# Sensor-PCB.net
KiCad netlist of a schematic drawn in Altium Designer
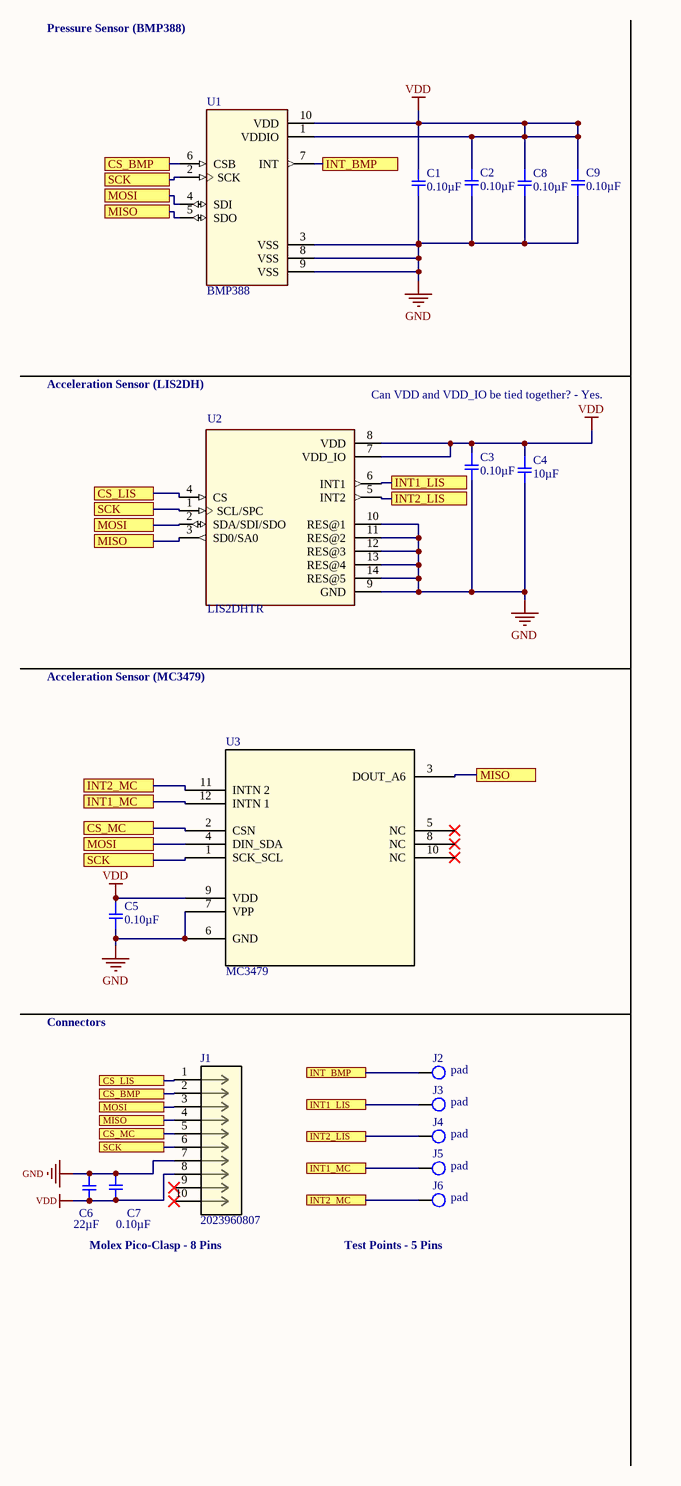
[diagram p0: Sensor-PCB.SchDoc]

(export (version "E")
  (design (tool "Eeschema 10.0.6"))
  (components
    (comp (ref "C1")
      (value "0.10µF")
      (footprint "SMD-0603C")
      (description "CAP CER 0.1UF 16V X7R 0603")
      (fields
        (field (name "DIGI-KEY PART NUMBER") "490-5796-1-ND")
        (field (name "PART NUMBER") "GCJ188R71C104KA01D")
      )
      (libsource (lib "capacitor_murata_0603") (part "GCJ188R71C104KA01D"))
    )
    (comp (ref "C2")
      (value "0.10µF")
      (footprint "SMD-0603C")
      (description "CAP CER 0.1UF 16V X7R 0603")
      (fields
        (field (name "DIGI-KEY PART NUMBER") "490-5796-1-ND")
        (field (name "PART NUMBER") "GCJ188R71C104KA01D")
      )
      (libsource (lib "capacitor_murata_0603") (part "GCJ188R71C104KA01D"))
    )
    (comp (ref "C3")
      (value "0.10µF")
      (footprint "SMD-0603C")
      (description "CAP CER 0.1UF 16V X7R 0603")
      (fields
        (field (name "DIGI-KEY PART NUMBER") "490-5796-1-ND")
        (field (name "PART NUMBER") "GCJ188R71C104KA01D")
      )
      (libsource (lib "capacitor_murata_0603") (part "GCJ188R71C104KA01D"))
    )
    (comp (ref "C4")
      (value "10µF")
      (footprint "SMD-0603C")
      (description "CAP CER 10UF 10V X6S 0603")
      (fields
        (field (name "DIGI-KEY PART NUMBER") "490-7197-1-ND")
        (field (name "PART NUMBER") "GRM188C81A106MA73D")
      )
      (libsource (lib "capacitor_murata_0603") (part "GRM188C81A106MA73D"))
    )
    (comp (ref "C5")
      (value "0.10µF")
      (footprint "SMD-0603C")
      (description "CAP CER 0.1UF 16V X7R 0603")
      (fields
        (field (name "DIGI-KEY PART NUMBER") "490-5796-1-ND")
        (field (name "PART NUMBER") "GCJ188R71C104KA01D")
      )
      (libsource (lib "capacitor_murata_0603") (part "GCJ188R71C104KA01D"))
    )
    (comp (ref "C6")
      (value "22µF")
      (footprint "SMD-0603C")
      (description "CAP CER 22UF 10V X5R 0603")
      (fields
        (field (name "DIGI-KEY PART NUMBER") "490-10476-1-ND")
        (field (name "PART NUMBER") "GRM188R61A226ME15D")
      )
      (libsource (lib "capacitor_murata_0603") (part "GRM188R61A226ME15D"))
    )
    (comp (ref "C7")
      (value "0.10µF")
      (footprint "SMD-0603C")
      (description "CAP CER 0.1UF 16V X7R 0603")
      (fields
        (field (name "DIGI-KEY PART NUMBER") "490-5796-1-ND")
        (field (name "PART NUMBER") "GCJ188R71C104KA01D")
      )
      (libsource (lib "capacitor_murata_0603") (part "GCJ188R71C104KA01D"))
    )
    (comp (ref "C8")
      (value "0.10µF")
      (footprint "SMD-0603C")
      (description "CAP CER 0.1UF 16V X7R 0603")
      (fields
        (field (name "DIGI-KEY PART NUMBER") "490-5796-1-ND")
        (field (name "PART NUMBER") "GCJ188R71C104KA01D")
      )
      (libsource (lib "capacitor_murata_0603") (part "GCJ188R71C104KA01D"))
    )
    (comp (ref "C9")
      (value "0.10µF")
      (footprint "SMD-0603C")
      (description "CAP CER 0.1UF 16V X7R 0603")
      (fields
        (field (name "DIGI-KEY PART NUMBER") "490-5796-1-ND")
        (field (name "PART NUMBER") "GCJ188R71C104KA01D")
      )
      (libsource (lib "capacitor_murata_0603") (part "GCJ188R71C104KA01D"))
    )
    (comp (ref "J1")
      (value "2023960807")
      (footprint "siplab_custom_parts:CON_2023960807")
      (description "No Description Available")
      (fields (field (name "COPYRIGHT") "Copyright (C) 2021 Ultra Librarian. All rights reserved."))
      (libsource (lib "2023960807") (part "2023960807"))
    )
    (comp (ref "J2")
      (value "pad")
      (footprint "pad rect 1.5x3mm - duplicate")
      (libsource (lib "siplab_custom_parts") (part "pad"))
    )
    (comp (ref "J3")
      (value "pad")
      (footprint "pad rect 1.5x3mm - duplicate")
      (libsource (lib "siplab_custom_parts") (part "pad"))
    )
    (comp (ref "J4")
      (value "pad")
      (footprint "pad rect 1.5x3mm - duplicate")
      (libsource (lib "siplab_custom_parts") (part "pad"))
    )
    (comp (ref "J5")
      (value "pad")
      (footprint "pad rect 1.5x3mm - duplicate")
      (libsource (lib "siplab_custom_parts") (part "pad"))
    )
    (comp (ref "J6")
      (value "pad")
      (footprint "pad rect 1.5x3mm - duplicate")
      (libsource (lib "siplab_custom_parts") (part "pad"))
    )
    (comp (ref "U1")
      (value "BMP388")
      (footprint "*PQFN50P200X200X80-10N")
      (description "P-Sensor SPI I2C 1, 25 Bar SMD")
      (fields (field (name "MF") "Bosch Sensortec") (field (name "DIGI-KEY_PART_NUMBER") "828-1079-1-ND"))
      (libsource (lib "siplab_custom_parts") (part "BMP388"))
    )
    (comp (ref "U2")
      (value "LIS2DHTR")
      (footprint "*PQFN35P200X200X100-14N")
      (description "ACCEL 2-16G I2C/SPI 14LGA")
      (fields
        (field (name "DIGI-KEY PART NUMBER") "497-13795-1-ND")
        (field (name "MANUFACTURER") "STMicroelectronics")
      )
      (libsource (lib "siplab_custom_parts") (part "LIS2DHTR"))
    )
    (comp (ref "U3")
      (value "MC3479")
      (footprint "MC3479_MEM")
      (description "No Description Available")
      (fields (field (name "COPYRIGHT") "Copyright (C) 2021 Ultra Librarian. All rights reserved."))
      (libsource (lib "siplab_custom_parts") (part "MC3479"))
    )
  )
  (nets
    (net (code "1") (name "/CS_BMP") (class "Default")
      (node (ref "J1") (pin "2") (pinfunction "2_2") (pintype "passive"))
      (node (ref "U1") (pin "6") (pinfunction "CSB_6") (pintype "input"))
    )
    (net (code "2") (name "/CS_LIS") (class "Default")
      (node (ref "J1") (pin "1") (pinfunction "1_1") (pintype "passive"))
      (node (ref "U2") (pin "4") (pinfunction "CS_4") (pintype "input"))
    )
    (net (code "3") (name "/CS_MC") (class "Default")
      (node (ref "J1") (pin "5") (pinfunction "5_5") (pintype "passive"))
      (node (ref "U3") (pin "2") (pinfunction "CSN_2") (pintype "passive"))
    )
    (net (code "4") (name "/INT1_LIS") (class "Default")
      (node (ref "J3") (pin "1") (pinfunction "1_1") (pintype "passive"))
      (node (ref "U2") (pin "6") (pinfunction "INT1_6") (pintype "output"))
    )
    (net (code "5") (name "/INT1_MC") (class "Default")
      (node (ref "J5") (pin "1") (pinfunction "1_1") (pintype "passive"))
      (node (ref "U3") (pin "12") (pinfunction "INTN_1_12") (pintype "passive"))
    )
    (net (code "6") (name "/INT2_LIS") (class "Default")
      (node (ref "J4") (pin "1") (pinfunction "1_1") (pintype "passive"))
      (node (ref "U2") (pin "5") (pinfunction "INT2_5") (pintype "output"))
    )
    (net (code "7") (name "/INT2_MC") (class "Default")
      (node (ref "J6") (pin "1") (pinfunction "1_1") (pintype "passive"))
      (node (ref "U3") (pin "11") (pinfunction "INTN_2_11") (pintype "passive"))
    )
    (net (code "8") (name "/INT_BMP") (class "Default")
      (node (ref "J2") (pin "1") (pinfunction "1_1") (pintype "passive"))
      (node (ref "U1") (pin "7") (pinfunction "INT_7") (pintype "output"))
    )
    (net (code "9") (name "/MISO") (class "Default")
      (node (ref "J1") (pin "4") (pinfunction "4_4") (pintype "passive"))
      (node (ref "U1") (pin "5") (pinfunction "SDO_5") (pintype "bidirectional"))
      (node (ref "U2") (pin "3") (pinfunction "SD0/SA0_3") (pintype "output"))
      (node (ref "U3") (pin "3") (pinfunction "DOUT_A6_3") (pintype "passive"))
    )
    (net (code "10") (name "/MOSI") (class "Default")
      (node (ref "J1") (pin "3") (pinfunction "3_3") (pintype "passive"))
      (node (ref "U1") (pin "4") (pinfunction "SDI_4") (pintype "bidirectional"))
      (node (ref "U2") (pin "2") (pinfunction "SDA/SDI/SDO_2") (pintype "bidirectional"))
      (node (ref "U3") (pin "4") (pinfunction "DIN_SDA_4") (pintype "passive"))
    )
    (net (code "11") (name "/SCK") (class "Default")
      (node (ref "J1") (pin "6") (pinfunction "6_6") (pintype "passive"))
      (node (ref "U1") (pin "2") (pinfunction "SCK_2") (pintype "input"))
      (node (ref "U2") (pin "1") (pinfunction "SCL/SPC_1") (pintype "input"))
      (node (ref "U3") (pin "1") (pinfunction "SCK_SCL_1") (pintype "passive"))
    )
    (net (code "12") (name "GND") (class "Default")
      (node (ref "C1") (pin "2") (pinfunction "2_2") (pintype "passive"))
      (node (ref "C2") (pin "2") (pinfunction "2_2") (pintype "passive"))
      (node (ref "C3") (pin "2") (pinfunction "2_2") (pintype "passive"))
      (node (ref "C4") (pin "2") (pinfunction "2_2") (pintype "passive"))
      (node (ref "C5") (pin "2") (pinfunction "2_2") (pintype "passive"))
      (node (ref "C6") (pin "1") (pinfunction "1_1") (pintype "passive"))
      (node (ref "C7") (pin "1") (pinfunction "1_1") (pintype "passive"))
      (node (ref "C8") (pin "2") (pinfunction "2_2") (pintype "passive"))
      (node (ref "C9") (pin "2") (pinfunction "2_2") (pintype "passive"))
      (node (ref "J1") (pin "7") (pinfunction "7_7") (pintype "passive"))
      (node (ref "U1") (pin "3") (pinfunction "VSS_3") (pintype "power_in"))
      (node (ref "U1") (pin "8") (pinfunction "VSS_8") (pintype "power_in"))
      (node (ref "U1") (pin "9") (pinfunction "VSS_9") (pintype "power_in"))
      (node (ref "U2") (pin "10") (pinfunction "RES@1_10") (pintype "power_in"))
      (node (ref "U2") (pin "11") (pinfunction "RES@2_11") (pintype "power_in"))
      (node (ref "U2") (pin "12") (pinfunction "RES@3_12") (pintype "power_in"))
      (node (ref "U2") (pin "13") (pinfunction "RES@4_13") (pintype "power_in"))
      (node (ref "U2") (pin "14") (pinfunction "RES@5_14") (pintype "power_in"))
      (node (ref "U2") (pin "9") (pinfunction "GND_9") (pintype "power_in"))
      (node (ref "U3") (pin "6") (pinfunction "GND_6") (pintype "passive"))
      (node (ref "U3") (pin "7") (pinfunction "VPP_7") (pintype "passive"))
    )
    (net (code "13") (name "VDD") (class "Default")
      (node (ref "C1") (pin "1") (pinfunction "1_1") (pintype "passive"))
      (node (ref "C2") (pin "1") (pinfunction "1_1") (pintype "passive"))
      (node (ref "C3") (pin "1") (pinfunction "1_1") (pintype "passive"))
      (node (ref "C4") (pin "1") (pinfunction "1_1") (pintype "passive"))
      (node (ref "C5") (pin "1") (pinfunction "1_1") (pintype "passive"))
      (node (ref "C6") (pin "2") (pinfunction "2_2") (pintype "passive"))
      (node (ref "C7") (pin "2") (pinfunction "2_2") (pintype "passive"))
      (node (ref "C8") (pin "1") (pinfunction "1_1") (pintype "passive"))
      (node (ref "C9") (pin "1") (pinfunction "1_1") (pintype "passive"))
      (node (ref "J1") (pin "8") (pinfunction "8_8") (pintype "passive"))
      (node (ref "U1") (pin "1") (pinfunction "VDDIO_1") (pintype "power_in"))
      (node (ref "U1") (pin "10") (pinfunction "VDD_10") (pintype "power_in"))
      (node (ref "U2") (pin "7") (pinfunction "VDD_IO_7") (pintype "power_in"))
      (node (ref "U2") (pin "8") (pinfunction "VDD_8") (pintype "power_in"))
      (node (ref "U3") (pin "9") (pinfunction "VDD_9") (pintype "passive"))
    )
    (net (code "14") (name "unconnected-(J1-Pad9)") (class "Default")
      (node (ref "J1") (pin "9") (pinfunction "9_9") (pintype "passive+no_connect"))
    )
    (net (code "15") (name "unconnected-(J1-Pad10)") (class "Default")
      (node (ref "J1") (pin "10") (pinfunction "10_10") (pintype "passive+no_connect"))
    )
    (net (code "16") (name "unconnected-(U3-NC-Pad5)") (class "Default")
      (node (ref "U3") (pin "5") (pinfunction "NC_5") (pintype "passive+no_connect"))
    )
    (net (code "17") (name "unconnected-(U3-NC-Pad8)") (class "Default")
      (node (ref "U3") (pin "8") (pinfunction "NC_8") (pintype "passive+no_connect"))
    )
    (net (code "18") (name "unconnected-(U3-NC-Pad10)") (class "Default")
      (node (ref "U3") (pin "10") (pinfunction "NC_10") (pintype "passive+no_connect"))
    )
  )
)
